# Geiger.net
KiCad netlist of a schematic drawn in EAGLE
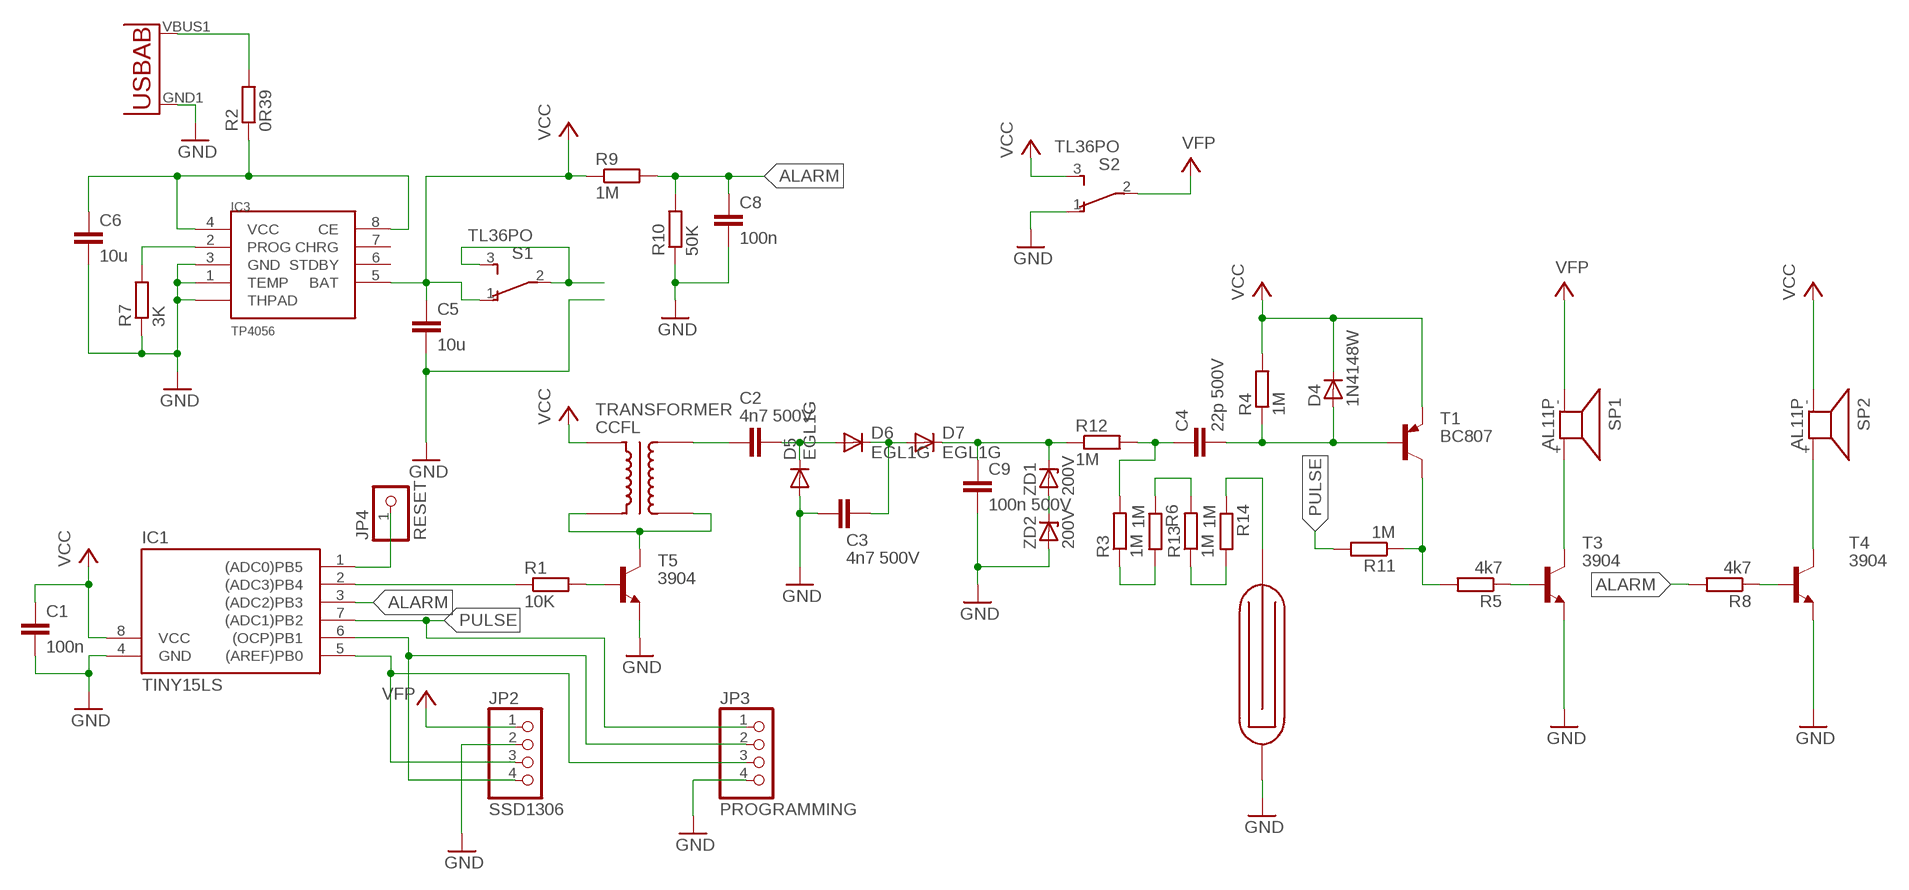
[diagram p0: schematic, sheet 1]

(export (version "E")
  (design (tool "Eeschema 10.0.6"))
  (components
    (comp (ref "C1")
      (value "100n")
      (footprint "eagle-import:C0805")
      (libsource (lib "eagle-import") (part "C-EUC0805"))
    )
    (comp (ref "C2")
      (value "4n7 500V")
      (footprint "eagle-import:C1206")
      (libsource (lib "eagle-import") (part "C-EUC1206"))
    )
    (comp (ref "C3")
      (value "4n7 500V")
      (footprint "eagle-import:C1206")
      (libsource (lib "eagle-import") (part "C-EUC1206"))
    )
    (comp (ref "C4")
      (value "22p 500V")
      (footprint "eagle-import:C050-024X044")
      (libsource (lib "eagle-import") (part "C-EU050-024X044"))
    )
    (comp (ref "C5")
      (value "10u")
      (footprint "eagle-import:C0805")
      (libsource (lib "eagle-import") (part "C-EUC0805"))
    )
    (comp (ref "C6")
      (value "10u")
      (footprint "eagle-import:C0805")
      (libsource (lib "eagle-import") (part "C-EUC0805"))
    )
    (comp (ref "C8")
      (value "100n")
      (footprint "eagle-import:C0805")
      (libsource (lib "eagle-import") (part "C-EUC0805"))
    )
    (comp (ref "C9")
      (value "100n 500V")
      (footprint "eagle-import:C150-054X183")
      (libsource (lib "eagle-import") (part "C-EU150-054X183"))
    )
    (comp (ref "D4")
      (value "1N4148W")
      (footprint "eagle-import:SOD123")
      (libsource (lib "eagle-import") (part "D-SOD123"))
    )
    (comp (ref "D5")
      (value "EGL1G")
      (footprint "eagle-import:SOD80C")
      (libsource (lib "eagle-import") (part "PMLL4150"))
    )
    (comp (ref "D6")
      (value "EGL1G")
      (footprint "eagle-import:SOD80C")
      (libsource (lib "eagle-import") (part "PMLL4150"))
    )
    (comp (ref "D7")
      (value "EGL1G")
      (footprint "eagle-import:SOD80C")
      (libsource (lib "eagle-import") (part "PMLL4150"))
    )
    (comp (ref "IC1")
      (value "TINY15LS")
      (footprint "eagle-import:SOIC8")
      (libsource (lib "eagle-import") (part "TINY15LS"))
    )
    (comp (ref "IC3")
      (value "TP4056")
      (footprint "eagle-import:SOP-8")
      (libsource (lib "eagle-import") (part "TP4056"))
    )
    (comp (ref "JP2")
      (value "SSD1306")
      (footprint "eagle-import:1X04")
      (libsource (lib "eagle-import") (part "PINHD-1X4"))
    )
    (comp (ref "JP3")
      (value "PROGRAMMING")
      (footprint "eagle-import:1X04")
      (libsource (lib "eagle-import") (part "PINHD-1X4"))
    )
    (comp (ref "JP4")
      (value "RESET")
      (footprint "eagle-import:1X01")
      (libsource (lib "eagle-import") (part "PINHD-1X1"))
    )
    (comp (ref "R1")
      (value "10K")
      (footprint "eagle-import:R0805")
      (libsource (lib "eagle-import") (part "R-EU_R0805"))
    )
    (comp (ref "R2")
      (value "0R39")
      (footprint "eagle-import:R1206")
      (libsource (lib "eagle-import") (part "R-EU_R1206"))
    )
    (comp (ref "R3")
      (value "1M")
      (footprint "eagle-import:R0805")
      (libsource (lib "eagle-import") (part "R-EU_R0805"))
    )
    (comp (ref "R4")
      (value "1M")
      (footprint "eagle-import:R0805")
      (libsource (lib "eagle-import") (part "R-EU_R0805"))
    )
    (comp (ref "R5")
      (value "4k7")
      (footprint "eagle-import:R0805")
      (libsource (lib "eagle-import") (part "R-EU_R0805"))
    )
    (comp (ref "R6")
      (value "1M")
      (footprint "eagle-import:R0805")
      (libsource (lib "eagle-import") (part "R-EU_R0805"))
    )
    (comp (ref "R7")
      (value "3K")
      (footprint "eagle-import:R0805")
      (libsource (lib "eagle-import") (part "R-EU_R0805"))
    )
    (comp (ref "R8")
      (value "4k7")
      (footprint "eagle-import:R0805")
      (libsource (lib "eagle-import") (part "R-EU_R0805"))
    )
    (comp (ref "R9")
      (value "1M")
      (footprint "eagle-import:R0805")
      (libsource (lib "eagle-import") (part "R-EU_R0805"))
    )
    (comp (ref "R10")
      (value "50K")
      (footprint "eagle-import:R0805")
      (libsource (lib "eagle-import") (part "R-EU_R0805"))
    )
    (comp (ref "R11")
      (value "1M")
      (footprint "eagle-import:R0805")
      (libsource (lib "eagle-import") (part "R-EU_R0805"))
    )
    (comp (ref "R12")
      (value "1M")
      (footprint "eagle-import:R0805")
      (libsource (lib "eagle-import") (part "R-EU_R0805"))
    )
    (comp (ref "R13")
      (value "1M")
      (footprint "eagle-import:R0805")
      (libsource (lib "eagle-import") (part "R-EU_R0805"))
    )
    (comp (ref "R14")
      (value "1M")
      (footprint "eagle-import:R0805")
      (libsource (lib "eagle-import") (part "R-EU_R0805"))
    )
    (comp (ref "S1")
      (value "TL36PO")
      (footprint "eagle-import:TL3XPO")
      (libsource (lib "eagle-import") (part "TL36PO"))
    )
    (comp (ref "S2")
      (value "TL36PO")
      (footprint "eagle-import:TL3XPO")
      (libsource (lib "eagle-import") (part "TL36PO"))
    )
    (comp (ref "SP1")
      (value "AL11P")
      (footprint "eagle-import:AL11P")
      (libsource (lib "eagle-import") (part "AL11P"))
    )
    (comp (ref "SP2")
      (value "AL11P")
      (footprint "eagle-import:AL11P")
      (libsource (lib "eagle-import") (part "AL11P"))
    )
    (comp (ref "T1")
      (value "BC807")
      (footprint "eagle-import:SOT23-BEC")
      (libsource (lib "eagle-import") (part "-PNP-SOT23-BECBC807-16"))
    )
    (comp (ref "T3")
      (value "3904")
      (footprint "eagle-import:SOT23-BEC")
      (libsource (lib "eagle-import") (part "-NPN-SOT23-BECMMBT3904LT1"))
    )
    (comp (ref "T4")
      (value "3904")
      (footprint "eagle-import:SOT23-BEC")
      (libsource (lib "eagle-import") (part "-NPN-SOT23-BECMMBT3904LT1"))
    )
    (comp (ref "T5")
      (value "3904")
      (footprint "eagle-import:SOT23-BEC")
      (libsource (lib "eagle-import") (part "-NPN-SOT23-BECMMBT3904LT1"))
    )
    (comp (ref "TRANSFORMER")
      (value "CCFL")
      (footprint "eagle-import:CCFL")
      (libsource (lib "eagle-import") (part "CCFL"))
    )
    (comp (ref "U$1")
      (value "SBM-20")
      (footprint "eagle-import:SBM-20")
      (libsource (lib "eagle-import") (part "SBM-20"))
    )
    (comp (ref "U2")
      (value "USB")
      (footprint "eagle-import:USB-MICRO-SMD")
      (libsource (lib "eagle-import") (part "USB{dblquote}{dblquote}"))
    )
    (comp (ref "ZD1")
      (value "200V")
      (footprint "eagle-import:MELF-MLL41")
      (libsource (lib "eagle-import") (part "ZD-MLL-41"))
    )
    (comp (ref "ZD2")
      (value "200V")
      (footprint "eagle-import:MELF-MLL41")
      (libsource (lib "eagle-import") (part "ZD-MLL-41"))
    )
  )
  (nets
    (net (code "1") (name "ALARM") (class "Default")
      (node (ref "C8") (pin "1") (pinfunction "1_1") (pintype "passive"))
      (node (ref "IC1") (pin "3") (pinfunction "(ADC2)PB3_3") (pintype "bidirectional"))
      (node (ref "R10") (pin "2") (pinfunction "2_2") (pintype "passive"))
      (node (ref "R8") (pin "2") (pinfunction "2_2") (pintype "passive"))
      (node (ref "R9") (pin "2") (pinfunction "2_2") (pintype "passive"))
    )
    (net (code "2") (name "GND") (class "Default")
      (node (ref "C1") (pin "2") (pinfunction "2_2") (pintype "passive"))
      (node (ref "C3") (pin "1") (pinfunction "1_1") (pintype "passive"))
      (node (ref "C5") (pin "2") (pinfunction "2_2") (pintype "passive"))
      (node (ref "C6") (pin "2") (pinfunction "2_2") (pintype "passive"))
      (node (ref "C8") (pin "2") (pinfunction "2_2") (pintype "passive"))
      (node (ref "C9") (pin "2") (pinfunction "2_2") (pintype "passive"))
      (node (ref "D5") (pin "A") (pinfunction "A_A") (pintype "passive"))
      (node (ref "IC1") (pin "4") (pinfunction "GND_4") (pintype "power_in"))
      (node (ref "IC3") (pin "1") (pinfunction "TEMP_1") (pintype "bidirectional"))
      (node (ref "IC3") (pin "3") (pinfunction "GND_3") (pintype "bidirectional"))
      (node (ref "IC3") (pin "P$1") (pinfunction "THPAD_P$1") (pintype "bidirectional"))
      (node (ref "JP2") (pin "2") (pinfunction "2_2") (pintype "passive"))
      (node (ref "JP3") (pin "4") (pinfunction "4_4") (pintype "passive"))
      (node (ref "R10") (pin "1") (pinfunction "1_1") (pintype "passive"))
      (node (ref "R7") (pin "1") (pinfunction "1_1") (pintype "passive"))
      (node (ref "S2") (pin "1") (pinfunction "O_1") (pintype "passive"))
      (node (ref "T3") (pin "E") (pinfunction "E_E") (pintype "passive"))
      (node (ref "T4") (pin "E") (pinfunction "E_E") (pintype "passive"))
      (node (ref "T5") (pin "E") (pinfunction "E_E") (pintype "passive"))
      (node (ref "U$1") (pin "P$2") (pinfunction "P$2_P$2") (pintype "bidirectional"))
      (node (ref "U2") (pin "GND1") (pinfunction "GND_GND1") (pintype "bidirectional"))
      (node (ref "ZD2") (pin "A") (pinfunction "A_A") (pintype "passive"))
    )
    (net (code "3") (name "Net-(C2-Pad1)") (class "Default")
      (node (ref "C2") (pin "1") (pinfunction "1_1") (pintype "passive"))
      (node (ref "TRANSFORMER") (pin "HV") (pinfunction "HV_HV") (pintype "bidirectional"))
    )
    (net (code "4") (name "Net-(C2-Pad2)") (class "Default")
      (node (ref "C2") (pin "2") (pinfunction "2_2") (pintype "passive"))
      (node (ref "D5") (pin "C") (pinfunction "C_C") (pintype "passive"))
      (node (ref "D6") (pin "A") (pinfunction "A_A") (pintype "passive"))
    )
    (net (code "5") (name "Net-(C3-Pad2)") (class "Default")
      (node (ref "C3") (pin "2") (pinfunction "2_2") (pintype "passive"))
      (node (ref "D6") (pin "C") (pinfunction "C_C") (pintype "passive"))
      (node (ref "D7") (pin "A") (pinfunction "A_A") (pintype "passive"))
    )
    (net (code "6") (name "Net-(C4-Pad1)") (class "Default")
      (node (ref "C4") (pin "1") (pinfunction "1_1") (pintype "passive"))
      (node (ref "R12") (pin "2") (pinfunction "2_2") (pintype "passive"))
      (node (ref "R3") (pin "2") (pinfunction "2_2") (pintype "passive"))
    )
    (net (code "7") (name "Net-(C4-Pad2)") (class "Default")
      (node (ref "C4") (pin "2") (pinfunction "2_2") (pintype "passive"))
      (node (ref "D4") (pin "A") (pinfunction "A_A") (pintype "passive"))
      (node (ref "R4") (pin "1") (pinfunction "1_1") (pintype "passive"))
      (node (ref "T1") (pin "B") (pinfunction "B_B") (pintype "passive"))
    )
    (net (code "8") (name "Net-(C9-Pad1)") (class "Default")
      (node (ref "C9") (pin "1") (pinfunction "1_1") (pintype "passive"))
      (node (ref "D7") (pin "C") (pinfunction "C_C") (pintype "passive"))
      (node (ref "R12") (pin "1") (pinfunction "1_1") (pintype "passive"))
      (node (ref "ZD1") (pin "C") (pinfunction "C_C") (pintype "passive"))
    )
    (net (code "9") (name "Net-(IC1-(ADC0)PB5)") (class "Default")
      (node (ref "IC1") (pin "1") (pinfunction "(ADC0)PB5_1") (pintype "bidirectional"))
      (node (ref "JP4") (pin "1") (pinfunction "1_1") (pintype "passive"))
    )
    (net (code "10") (name "Net-(IC1-(ADC3)PB4)") (class "Default")
      (node (ref "IC1") (pin "2") (pinfunction "(ADC3)PB4_2") (pintype "bidirectional"))
      (node (ref "R1") (pin "1") (pinfunction "1_1") (pintype "passive"))
    )
    (net (code "11") (name "Net-(IC1-(AREF)PB0)") (class "Default")
      (node (ref "IC1") (pin "5") (pinfunction "(AREF)PB0_5") (pintype "bidirectional"))
      (node (ref "JP2") (pin "3") (pinfunction "3_3") (pintype "passive"))
      (node (ref "JP3") (pin "3") (pinfunction "3_3") (pintype "passive"))
    )
    (net (code "12") (name "Net-(IC1-(OCP)PB1)") (class "Default")
      (node (ref "IC1") (pin "6") (pinfunction "(OCP)PB1_6") (pintype "bidirectional"))
      (node (ref "JP2") (pin "4") (pinfunction "4_4") (pintype "passive"))
      (node (ref "JP3") (pin "2") (pinfunction "2_2") (pintype "passive"))
    )
    (net (code "13") (name "Net-(IC3-CE)") (class "Default")
      (node (ref "C6") (pin "1") (pinfunction "1_1") (pintype "passive"))
      (node (ref "IC3") (pin "4") (pinfunction "VCC_4") (pintype "bidirectional"))
      (node (ref "IC3") (pin "8") (pinfunction "CE_8") (pintype "bidirectional"))
      (node (ref "R2") (pin "1") (pinfunction "1_1") (pintype "passive"))
    )
    (net (code "14") (name "Net-(IC3-PROG)") (class "Default")
      (node (ref "IC3") (pin "2") (pinfunction "PROG_2") (pintype "bidirectional"))
      (node (ref "R7") (pin "2") (pinfunction "2_2") (pintype "passive"))
    )
    (net (code "15") (name "Net-(R1-Pad2)") (class "Default")
      (node (ref "R1") (pin "2") (pinfunction "2_2") (pintype "passive"))
      (node (ref "T5") (pin "B") (pinfunction "B_B") (pintype "passive"))
    )
    (net (code "16") (name "Net-(R3-Pad1)") (class "Default")
      (node (ref "R3") (pin "1") (pinfunction "1_1") (pintype "passive"))
      (node (ref "R6") (pin "2") (pinfunction "2_2") (pintype "passive"))
    )
    (net (code "17") (name "Net-(R5-Pad1)") (class "Default")
      (node (ref "R5") (pin "1") (pinfunction "1_1") (pintype "passive"))
      (node (ref "T3") (pin "B") (pinfunction "B_B") (pintype "passive"))
    )
    (net (code "18") (name "Net-(R8-Pad1)") (class "Default")
      (node (ref "R8") (pin "1") (pinfunction "1_1") (pintype "passive"))
      (node (ref "T4") (pin "B") (pinfunction "B_B") (pintype "passive"))
    )
    (net (code "19") (name "Net-(R11-Pad1)") (class "Default")
      (node (ref "R11") (pin "1") (pinfunction "1_1") (pintype "passive"))
      (node (ref "R5") (pin "2") (pinfunction "2_2") (pintype "passive"))
      (node (ref "T1") (pin "C") (pinfunction "C_C") (pintype "passive"))
    )
    (net (code "20") (name "Net-(R13-Pad1)") (class "Default")
      (node (ref "R13") (pin "1") (pinfunction "1_1") (pintype "passive"))
      (node (ref "R14") (pin "2") (pinfunction "2_2") (pintype "passive"))
    )
    (net (code "21") (name "Net-(R13-Pad2)") (class "Default")
      (node (ref "R13") (pin "2") (pinfunction "2_2") (pintype "passive"))
      (node (ref "R6") (pin "1") (pinfunction "1_1") (pintype "passive"))
    )
    (net (code "22") (name "Net-(R14-Pad1)") (class "Default")
      (node (ref "R14") (pin "1") (pinfunction "1_1") (pintype "passive"))
      (node (ref "U$1") (pin "P$1") (pinfunction "P$1_P$1") (pintype "bidirectional"))
    )
    (net (code "23") (name "Net-(S1-P)") (class "Default")
      (node (ref "S1") (pin "2") (pinfunction "P_2") (pintype "passive"))
      (node (ref "S1") (pin "3") (pinfunction "S_3") (pintype "passive"))
    )
    (net (code "24") (name "Net-(SP1-2)") (class "Default")
      (node (ref "SP1") (pin "+") (pinfunction "2_+") (pintype "passive"))
      (node (ref "T3") (pin "C") (pinfunction "C_C") (pintype "passive"))
    )
    (net (code "25") (name "Net-(SP2-2)") (class "Default")
      (node (ref "SP2") (pin "+") (pinfunction "2_+") (pintype "passive"))
      (node (ref "T4") (pin "C") (pinfunction "C_C") (pintype "passive"))
    )
    (net (code "26") (name "Net-(T5-PadC)") (class "Default")
      (node (ref "T5") (pin "C") (pinfunction "C_C") (pintype "passive"))
      (node (ref "TRANSFORMER") (pin "TR1") (pinfunction "TR1_TR1") (pintype "bidirectional"))
      (node (ref "TRANSFORMER") (pin "TR2") (pinfunction "TR2_TR2") (pintype "bidirectional"))
    )
    (net (code "27") (name "Net-(U2-VBUS)") (class "Default")
      (node (ref "R2") (pin "2") (pinfunction "2_2") (pintype "passive"))
      (node (ref "U2") (pin "VBUS1") (pinfunction "VBUS_VBUS1") (pintype "bidirectional"))
    )
    (net (code "28") (name "Net-(ZD1-PadA)") (class "Default")
      (node (ref "ZD1") (pin "A") (pinfunction "A_A") (pintype "passive"))
      (node (ref "ZD2") (pin "C") (pinfunction "C_C") (pintype "passive"))
    )
    (net (code "29") (name "PULSE") (class "Default")
      (node (ref "IC1") (pin "7") (pinfunction "(ADC1)PB2_7") (pintype "bidirectional"))
      (node (ref "JP3") (pin "1") (pinfunction "1_1") (pintype "passive"))
      (node (ref "R11") (pin "2") (pinfunction "2_2") (pintype "passive"))
    )
    (net (code "30") (name "VCC") (class "Default")
      (node (ref "C1") (pin "1") (pinfunction "1_1") (pintype "passive"))
      (node (ref "C5") (pin "1") (pinfunction "1_1") (pintype "passive"))
      (node (ref "D4") (pin "C") (pinfunction "C_C") (pintype "passive"))
      (node (ref "IC1") (pin "8") (pinfunction "VCC_8") (pintype "power_in"))
      (node (ref "IC3") (pin "5") (pinfunction "BAT_5") (pintype "bidirectional"))
      (node (ref "R4") (pin "2") (pinfunction "2_2") (pintype "passive"))
      (node (ref "R9") (pin "1") (pinfunction "1_1") (pintype "passive"))
      (node (ref "S1") (pin "1") (pinfunction "O_1") (pintype "passive"))
      (node (ref "S2") (pin "3") (pinfunction "S_3") (pintype "passive"))
      (node (ref "SP2") (pin "-") (pinfunction "1_-") (pintype "passive"))
      (node (ref "T1") (pin "E") (pinfunction "E_E") (pintype "passive"))
      (node (ref "TRANSFORMER") (pin "V+") (pinfunction "V+_V+") (pintype "bidirectional"))
    )
    (net (code "31") (name "VFP") (class "Default")
      (node (ref "JP2") (pin "1") (pinfunction "1_1") (pintype "passive"))
      (node (ref "S2") (pin "2") (pinfunction "P_2") (pintype "passive"))
      (node (ref "SP1") (pin "-") (pinfunction "1_-") (pintype "passive"))
    )
    (net (code "32") (name "unconnected-(IC3-CHRG-Pad7)") (class "Default")
      (node (ref "IC3") (pin "7") (pinfunction "CHRG_7") (pintype "bidirectional"))
    )
    (net (code "33") (name "unconnected-(IC3-STDBY-Pad6)") (class "Default")
      (node (ref "IC3") (pin "6") (pinfunction "STDBY_6") (pintype "bidirectional"))
    )
  )
)
